# main.net
KiCad netlist of a schematic drawn in EAGLE
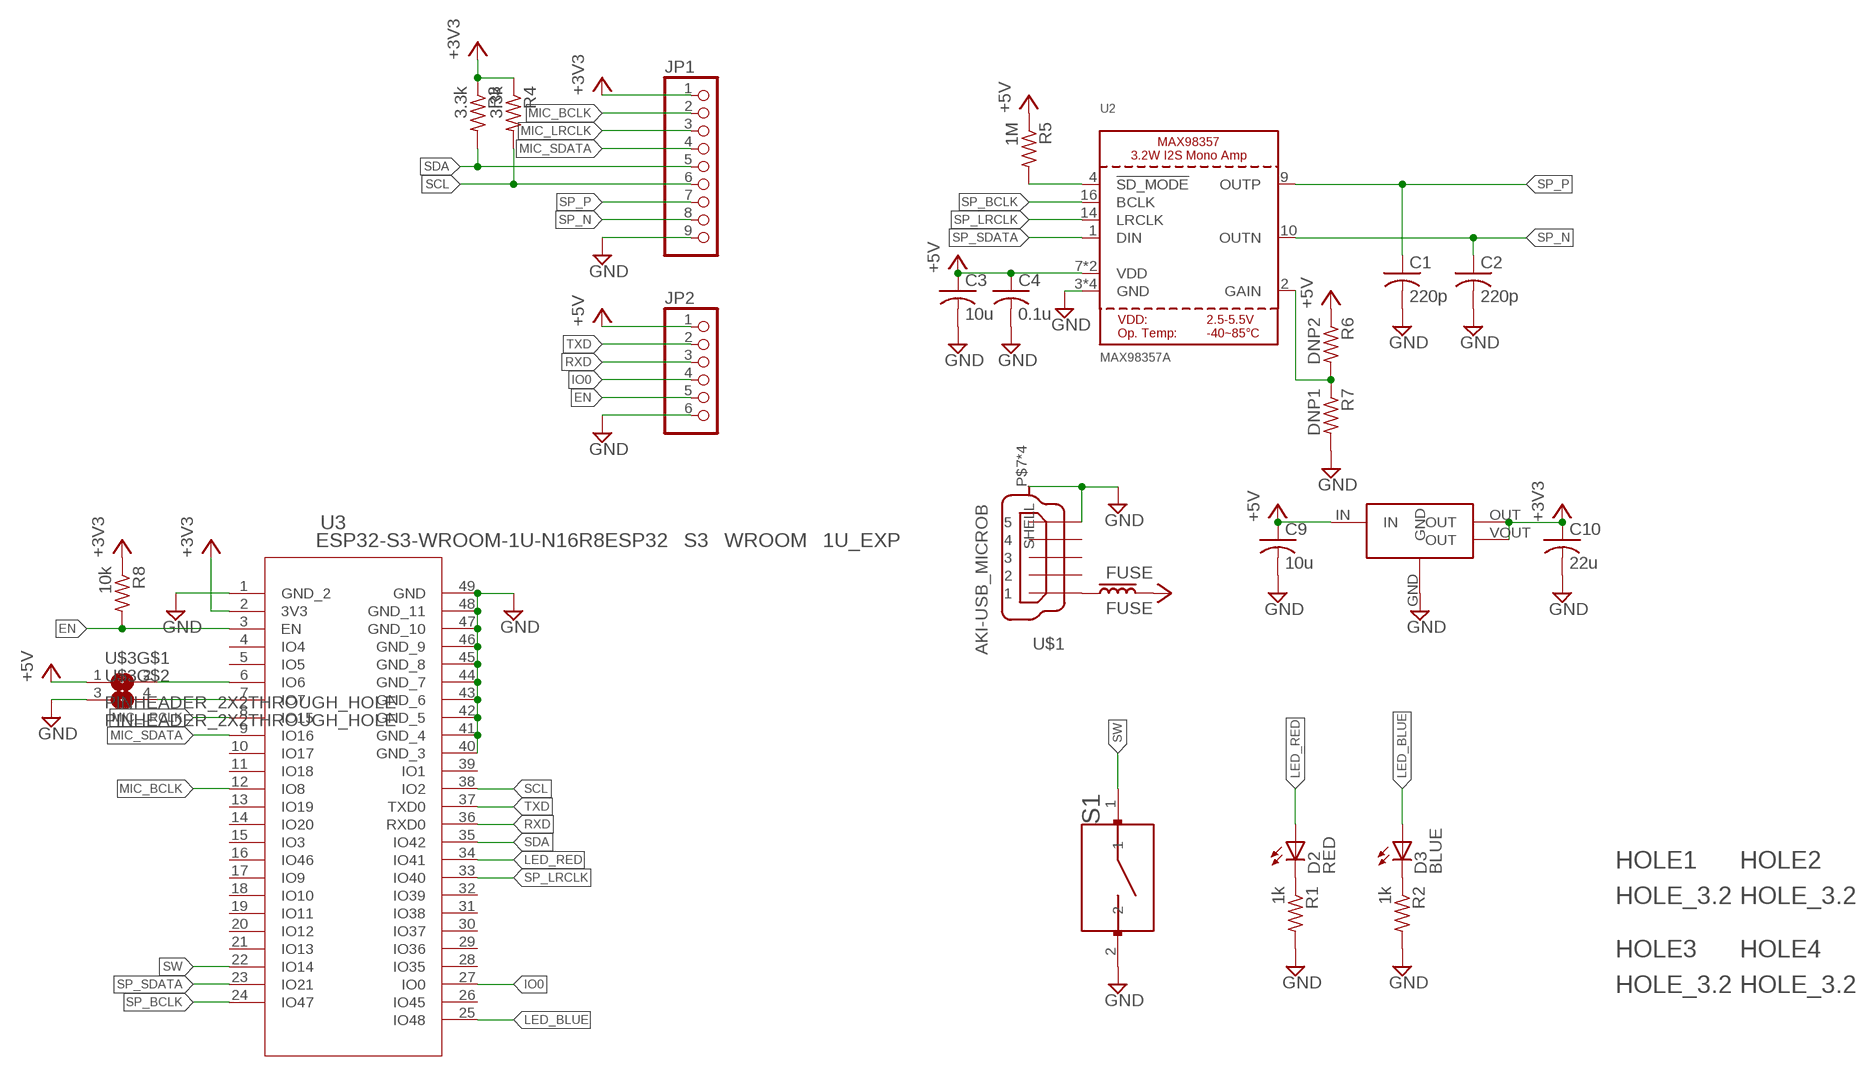
[diagram p0: schematic, sheet 1]

(export (version "E")
  (design (tool "Eeschema 10.0.6"))
  (components
    (comp (ref "C1")
      (value "220p")
      (footprint "eagle-import:2012-C")
      (libsource (lib "eagle-import") (part "C-2012"))
    )
    (comp (ref "C2")
      (value "220p")
      (footprint "eagle-import:2012-C")
      (libsource (lib "eagle-import") (part "C-2012"))
    )
    (comp (ref "C3")
      (value "10u")
      (footprint "eagle-import:2012-C")
      (libsource (lib "eagle-import") (part "C-2012"))
    )
    (comp (ref "C4")
      (value "0.1u")
      (footprint "eagle-import:2012-C")
      (libsource (lib "eagle-import") (part "C-2012"))
    )
    (comp (ref "C9")
      (value "10u")
      (footprint "eagle-import:2012-C")
      (libsource (lib "eagle-import") (part "C-2012"))
    )
    (comp (ref "C10")
      (value "22u")
      (footprint "eagle-import:2012-C")
      (libsource (lib "eagle-import") (part "C-2012"))
    )
    (comp (ref "D2")
      (value "RED")
      (footprint "eagle-import:D2012")
      (libsource (lib "eagle-import") (part "LED-SMD2012"))
    )
    (comp (ref "D3")
      (value "BLUE")
      (footprint "eagle-import:D2012")
      (libsource (lib "eagle-import") (part "LED-SMD2012"))
    )
    (comp (ref "FUSE")
      (value "FUSE")
      (footprint "eagle-import:2012-C")
      (libsource (lib "eagle-import") (part "FB-2012"))
    )
    (comp (ref "HOLE1")
      (value "HOLE_3.2")
      (footprint "eagle-import:HOLE_3.2")
      (libsource (lib "eagle-import") (part "HOLE_3.2"))
    )
    (comp (ref "HOLE2")
      (value "HOLE_3.2")
      (footprint "eagle-import:HOLE_3.2")
      (libsource (lib "eagle-import") (part "HOLE_3.2"))
    )
    (comp (ref "HOLE3")
      (value "HOLE_3.2")
      (footprint "eagle-import:HOLE_3.2")
      (libsource (lib "eagle-import") (part "HOLE_3.2"))
    )
    (comp (ref "HOLE4")
      (value "HOLE_3.2")
      (footprint "eagle-import:HOLE_3.2")
      (libsource (lib "eagle-import") (part "HOLE_3.2"))
    )
    (comp (ref "IC2")
      (value "AZ1117H-ADJ")
      (footprint "eagle-import:SOT223")
      (libsource (lib "eagle-import") (part "AZ1117H-ADJ"))
    )
    (comp (ref "JP1")
      (value "PINHD-1X9")
      (footprint "eagle-import:1X09")
      (libsource (lib "eagle-import") (part "PINHD-1X9"))
    )
    (comp (ref "JP2")
      (value "PINHD-1X6")
      (footprint "eagle-import:1X06")
      (libsource (lib "eagle-import") (part "PINHD-1X6"))
    )
    (comp (ref "R1")
      (value "1k")
      (footprint "eagle-import:2012-R")
      (libsource (lib "eagle-import") (part "R-2012"))
    )
    (comp (ref "R2")
      (value "1k")
      (footprint "eagle-import:2012-R")
      (libsource (lib "eagle-import") (part "R-2012"))
    )
    (comp (ref "R3")
      (value "3.3k")
      (footprint "eagle-import:2012-R")
      (libsource (lib "eagle-import") (part "R-2012"))
    )
    (comp (ref "R4")
      (value "3.3k")
      (footprint "eagle-import:2012-R")
      (libsource (lib "eagle-import") (part "R-2012"))
    )
    (comp (ref "R5")
      (value "1M")
      (footprint "eagle-import:2012-R")
      (libsource (lib "eagle-import") (part "R-2012"))
    )
    (comp (ref "R6")
      (value "DNP2")
      (footprint "eagle-import:2012-R")
      (libsource (lib "eagle-import") (part "R-2012"))
    )
    (comp (ref "R7")
      (value "DNP1")
      (footprint "eagle-import:2012-R")
      (libsource (lib "eagle-import") (part "R-2012"))
    )
    (comp (ref "R8")
      (value "10k")
      (footprint "eagle-import:2012-R")
      (libsource (lib "eagle-import") (part "R-2012"))
    )
    (comp (ref "S1")
      (value "TACTSW_SMD")
      (footprint "eagle-import:SW_B3U-1000P")
      (fields
        (field (name "DIGI-KEY_PART_NUMBER") "SW1021CT-ND")
        (field (name "MF") "Omron")
        (field (name "MP") "B3U-1100P")
      )
      (libsource (lib "eagle-import") (part "TACTSW_SMD"))
    )
    (comp (ref "U$1")
      (value "AKI-USB_MICROB")
      (footprint "eagle-import:ZX62R_B")
      (libsource (lib "eagle-import") (part "AKI-USB_MICROB"))
    )
    (comp (ref "U$3")
      (value "PINHEADER_2X2THROUGH_HOLE")
      (footprint "eagle-import:2X02")
      (libsource (lib "eagle-import") (part "PINHEADER_2X2THROUGH_HOLE"))
    )
    (comp (ref "U2")
      (value "MAX98357A")
      (footprint "eagle-import:QFN16_3MM")
      (libsource (lib "eagle-import") (part "AUDIOAMP_MAX98357"))
    )
    (comp (ref "U3")
      (value "ESP32-S3-WROOM-1U-N16R8ESP32�S3�WROOM�1U_EXP")
      (footprint "eagle-import:ESP32�S3�WROOM�1U_EXP")
      (fields
        (field (name "MANUFACTURER_PART_NUMBER") "ESP32-S3-WROOM-1U-N16R8")
        (field (name "COPYRIGHT") "Copyright (C) 2023 Ultra Librarian. All rights reserved.")
      )
      (libsource (lib "eagle-import") (part "ESP32-S3-WROOM-1U-N16R8ESP32�S3�WROOM�1U_EXP"))
    )
  )
  (nets
    (net (code "1") (name "+3V3") (class "Default")
      (node (ref "C10") (pin "1") (pinfunction "1_1") (pintype "passive"))
      (node (ref "IC2") (pin "OUT") (pinfunction "OUT_OUT") (pintype "power_in"))
      (node (ref "IC2") (pin "VOUT") (pinfunction "OUT_VOUT") (pintype "power_in"))
      (node (ref "JP1") (pin "1") (pinfunction "1_1") (pintype "passive"))
      (node (ref "R3") (pin "1") (pinfunction "1_1") (pintype "passive"))
      (node (ref "R4") (pin "1") (pinfunction "1_1") (pintype "passive"))
      (node (ref "R8") (pin "1") (pinfunction "1_1") (pintype "passive"))
      (node (ref "U3") (pin "2") (pinfunction "3V3_2") (pintype "power_in"))
    )
    (net (code "2") (name "+5V") (class "Default")
      (node (ref "C3") (pin "1") (pinfunction "1_1") (pintype "passive"))
      (node (ref "C4") (pin "1") (pinfunction "1_1") (pintype "passive"))
      (node (ref "C9") (pin "1") (pinfunction "1_1") (pintype "passive"))
      (node (ref "FUSE") (pin "2") (pinfunction "2_2") (pintype "passive"))
      (node (ref "IC2") (pin "IN") (pinfunction "IN_IN") (pintype "power_in"))
      (node (ref "JP2") (pin "1") (pinfunction "1_1") (pintype "passive"))
      (node (ref "R5") (pin "1") (pinfunction "1_1") (pintype "passive"))
      (node (ref "R6") (pin "1") (pinfunction "1_1") (pintype "passive"))
      (node (ref "U$3") (pin "1") (pinfunction "1_1") (pintype "passive"))
      (node (ref "U2") (pin "7") (pinfunction "VDD_7") (pintype "power_in"))
      (node (ref "U2") (pin "8") (pinfunction "VDD_8") (pintype "power_in"))
    )
    (net (code "3") (name "EN") (class "Default")
      (node (ref "JP2") (pin "5") (pinfunction "5_5") (pintype "passive"))
      (node (ref "R8") (pin "2") (pinfunction "2_2") (pintype "passive"))
      (node (ref "U3") (pin "3") (pinfunction "EN_3") (pintype "input"))
    )
    (net (code "4") (name "GND") (class "Default")
      (node (ref "C1") (pin "2") (pinfunction "2_2") (pintype "passive"))
      (node (ref "C10") (pin "2") (pinfunction "2_2") (pintype "passive"))
      (node (ref "C2") (pin "2") (pinfunction "2_2") (pintype "passive"))
      (node (ref "C3") (pin "2") (pinfunction "2_2") (pintype "passive"))
      (node (ref "C4") (pin "2") (pinfunction "2_2") (pintype "passive"))
      (node (ref "C9") (pin "2") (pinfunction "2_2") (pintype "passive"))
      (node (ref "IC2") (pin "GND") (pinfunction "GND_GND") (pintype "power_in"))
      (node (ref "JP1") (pin "9") (pinfunction "9_9") (pintype "passive"))
      (node (ref "JP2") (pin "6") (pinfunction "6_6") (pintype "passive"))
      (node (ref "R1") (pin "2") (pinfunction "2_2") (pintype "passive"))
      (node (ref "R2") (pin "2") (pinfunction "2_2") (pintype "passive"))
      (node (ref "R7") (pin "2") (pinfunction "2_2") (pintype "passive"))
      (node (ref "S1") (pin "2") (pinfunction "2_2") (pintype "passive"))
      (node (ref "U$1") (pin "5") (pinfunction "5_5") (pintype "input"))
      (node (ref "U$1") (pin "P$7") (pinfunction "SHELL_P$7") (pintype "bidirectional"))
      (node (ref "U$1") (pin "P$8") (pinfunction "SHELL_P$8") (pintype "bidirectional"))
      (node (ref "U$1") (pin "P$9") (pinfunction "SHELL_P$9") (pintype "bidirectional"))
      (node (ref "U$1") (pin "SH") (pinfunction "SHELL_SH") (pintype "bidirectional"))
      (node (ref "U$3") (pin "3") (pinfunction "1_3") (pintype "passive"))
      (node (ref "U2") (pin "11") (pinfunction "GND_11") (pintype "power_in"))
      (node (ref "U2") (pin "15") (pinfunction "GND_15") (pintype "power_in"))
      (node (ref "U2") (pin "3") (pinfunction "GND_3") (pintype "power_in"))
      (node (ref "U2") (pin "THERMAL") (pinfunction "GND_THERMAL") (pintype "power_in"))
      (node (ref "U3") (pin "1") (pinfunction "GND_2_1") (pintype "passive"))
      (node (ref "U3") (pin "40") (pinfunction "GND_3_40") (pintype "passive"))
      (node (ref "U3") (pin "41") (pinfunction "GND_4_41") (pintype "passive"))
      (node (ref "U3") (pin "42") (pinfunction "GND_5_42") (pintype "passive"))
      (node (ref "U3") (pin "43") (pinfunction "GND_6_43") (pintype "passive"))
      (node (ref "U3") (pin "44") (pinfunction "GND_7_44") (pintype "passive"))
      (node (ref "U3") (pin "45") (pinfunction "GND_8_45") (pintype "passive"))
      (node (ref "U3") (pin "46") (pinfunction "GND_9_46") (pintype "passive"))
      (node (ref "U3") (pin "47") (pinfunction "GND_10_47") (pintype "passive"))
      (node (ref "U3") (pin "48") (pinfunction "GND_11_48") (pintype "passive"))
      (node (ref "U3") (pin "49") (pinfunction "GND_49") (pintype "passive"))
    )
    (net (code "5") (name "IO0") (class "Default")
      (node (ref "JP2") (pin "4") (pinfunction "4_4") (pintype "passive"))
      (node (ref "U3") (pin "27") (pinfunction "IO0_27") (pintype "bidirectional"))
    )
    (net (code "6") (name "LED_BLUE") (class "Default")
      (node (ref "D3") (pin "A") (pinfunction "A_A") (pintype "passive"))
      (node (ref "U3") (pin "25") (pinfunction "IO48_25") (pintype "bidirectional"))
    )
    (net (code "7") (name "LED_RED") (class "Default")
      (node (ref "D2") (pin "A") (pinfunction "A_A") (pintype "passive"))
      (node (ref "U3") (pin "34") (pinfunction "IO41_34") (pintype "bidirectional"))
    )
    (net (code "8") (name "MIC_BCLK") (class "Default")
      (node (ref "JP1") (pin "2") (pinfunction "2_2") (pintype "passive"))
      (node (ref "U3") (pin "12") (pinfunction "IO8_12") (pintype "bidirectional"))
    )
    (net (code "9") (name "MIC_LRCLK") (class "Default")
      (node (ref "JP1") (pin "3") (pinfunction "3_3") (pintype "passive"))
      (node (ref "U3") (pin "8") (pinfunction "IO15_8") (pintype "bidirectional"))
    )
    (net (code "10") (name "MIC_SDATA") (class "Default")
      (node (ref "JP1") (pin "4") (pinfunction "4_4") (pintype "passive"))
      (node (ref "U3") (pin "9") (pinfunction "IO16_9") (pintype "bidirectional"))
    )
    (net (code "11") (name "Net-(D2-PadK)") (class "Default")
      (node (ref "D2") (pin "K") (pinfunction "K_K") (pintype "passive"))
      (node (ref "R1") (pin "1") (pinfunction "1_1") (pintype "passive"))
    )
    (net (code "12") (name "Net-(D3-PadK)") (class "Default")
      (node (ref "D3") (pin "K") (pinfunction "K_K") (pintype "passive"))
      (node (ref "R2") (pin "1") (pinfunction "1_1") (pintype "passive"))
    )
    (net (code "13") (name "Net-(FUSE-Pad1)") (class "Default")
      (node (ref "FUSE") (pin "1") (pinfunction "1_1") (pintype "passive"))
      (node (ref "U$1") (pin "1") (pinfunction "1_1") (pintype "input"))
    )
    (net (code "14") (name "Net-(U$3B-2)") (class "Default")
      (node (ref "U$3") (pin "4") (pinfunction "2_4") (pintype "passive"))
      (node (ref "U3") (pin "7") (pinfunction "IO7_7") (pintype "bidirectional"))
    )
    (net (code "15") (name "Net-(U2-GAIN)") (class "Default")
      (node (ref "R6") (pin "2") (pinfunction "2_2") (pintype "passive"))
      (node (ref "R7") (pin "1") (pinfunction "1_1") (pintype "passive"))
      (node (ref "U2") (pin "2") (pinfunction "GAIN_2") (pintype "bidirectional"))
    )
    (net (code "16") (name "Net-(U2-~{SD_MODE})") (class "Default")
      (node (ref "R5") (pin "2") (pinfunction "2_2") (pintype "passive"))
      (node (ref "U2") (pin "4") (pinfunction "~{SD_MODE}_4") (pintype "bidirectional"))
    )
    (net (code "17") (name "Net-(U3-IO6)") (class "Default")
      (node (ref "U$3") (pin "2") (pinfunction "2_2") (pintype "passive"))
      (node (ref "U3") (pin "6") (pinfunction "IO6_6") (pintype "bidirectional"))
    )
    (net (code "18") (name "RXD") (class "Default")
      (node (ref "JP2") (pin "3") (pinfunction "3_3") (pintype "passive"))
      (node (ref "U3") (pin "36") (pinfunction "RXD0_36") (pintype "bidirectional"))
    )
    (net (code "19") (name "SCL") (class "Default")
      (node (ref "JP1") (pin "6") (pinfunction "6_6") (pintype "passive"))
      (node (ref "R4") (pin "2") (pinfunction "2_2") (pintype "passive"))
      (node (ref "U3") (pin "38") (pinfunction "IO2_38") (pintype "bidirectional"))
    )
    (net (code "20") (name "SDA") (class "Default")
      (node (ref "JP1") (pin "5") (pinfunction "5_5") (pintype "passive"))
      (node (ref "R3") (pin "2") (pinfunction "2_2") (pintype "passive"))
      (node (ref "U3") (pin "35") (pinfunction "IO42_35") (pintype "bidirectional"))
    )
    (net (code "21") (name "SP_BCLK") (class "Default")
      (node (ref "U2") (pin "16") (pinfunction "BCLK_16") (pintype "bidirectional"))
      (node (ref "U3") (pin "24") (pinfunction "IO47_24") (pintype "bidirectional"))
    )
    (net (code "22") (name "SP_LRCLK") (class "Default")
      (node (ref "U2") (pin "14") (pinfunction "LRCLK_14") (pintype "bidirectional"))
      (node (ref "U3") (pin "33") (pinfunction "IO40_33") (pintype "bidirectional"))
    )
    (net (code "23") (name "SP_N") (class "Default")
      (node (ref "C2") (pin "1") (pinfunction "1_1") (pintype "passive"))
      (node (ref "JP1") (pin "8") (pinfunction "8_8") (pintype "passive"))
      (node (ref "U2") (pin "10") (pinfunction "OUTN_10") (pintype "output"))
    )
    (net (code "24") (name "SP_P") (class "Default")
      (node (ref "C1") (pin "1") (pinfunction "1_1") (pintype "passive"))
      (node (ref "JP1") (pin "7") (pinfunction "7_7") (pintype "passive"))
      (node (ref "U2") (pin "9") (pinfunction "OUTP_9") (pintype "output"))
    )
    (net (code "25") (name "SP_SDATA") (class "Default")
      (node (ref "U2") (pin "1") (pinfunction "DIN_1") (pintype "bidirectional"))
      (node (ref "U3") (pin "23") (pinfunction "IO21_23") (pintype "bidirectional"))
    )
    (net (code "26") (name "SW") (class "Default")
      (node (ref "S1") (pin "1") (pinfunction "1_1") (pintype "passive"))
      (node (ref "U3") (pin "22") (pinfunction "IO14_22") (pintype "bidirectional"))
    )
    (net (code "27") (name "TXD") (class "Default")
      (node (ref "JP2") (pin "2") (pinfunction "2_2") (pintype "passive"))
      (node (ref "U3") (pin "37") (pinfunction "TXD0_37") (pintype "bidirectional"))
    )
    (net (code "28") (name "unconnected-(U$1-Pad2)") (class "Default")
      (node (ref "U$1") (pin "2") (pinfunction "2_2") (pintype "input"))
    )
    (net (code "29") (name "unconnected-(U$1-Pad3)") (class "Default")
      (node (ref "U$1") (pin "3") (pinfunction "3_3") (pintype "input"))
    )
    (net (code "30") (name "unconnected-(U$1-Pad4)") (class "Default")
      (node (ref "U$1") (pin "4") (pinfunction "4_4") (pintype "input"))
    )
    (net (code "31") (name "unconnected-(U3-IO1-Pad39)") (class "Default")
      (node (ref "U3") (pin "39") (pinfunction "IO1_39") (pintype "bidirectional"))
    )
    (net (code "32") (name "unconnected-(U3-IO3-Pad15)") (class "Default")
      (node (ref "U3") (pin "15") (pinfunction "IO3_15") (pintype "bidirectional"))
    )
    (net (code "33") (name "unconnected-(U3-IO4-Pad4)") (class "Default")
      (node (ref "U3") (pin "4") (pinfunction "IO4_4") (pintype "bidirectional"))
    )
    (net (code "34") (name "unconnected-(U3-IO5-Pad5)") (class "Default")
      (node (ref "U3") (pin "5") (pinfunction "IO5_5") (pintype "bidirectional"))
    )
    (net (code "35") (name "unconnected-(U3-IO9-Pad17)") (class "Default")
      (node (ref "U3") (pin "17") (pinfunction "IO9_17") (pintype "bidirectional"))
    )
    (net (code "36") (name "unconnected-(U3-IO10-Pad18)") (class "Default")
      (node (ref "U3") (pin "18") (pinfunction "IO10_18") (pintype "bidirectional"))
    )
    (net (code "37") (name "unconnected-(U3-IO11-Pad19)") (class "Default")
      (node (ref "U3") (pin "19") (pinfunction "IO11_19") (pintype "bidirectional"))
    )
    (net (code "38") (name "unconnected-(U3-IO12-Pad20)") (class "Default")
      (node (ref "U3") (pin "20") (pinfunction "IO12_20") (pintype "bidirectional"))
    )
    (net (code "39") (name "unconnected-(U3-IO13-Pad21)") (class "Default")
      (node (ref "U3") (pin "21") (pinfunction "IO13_21") (pintype "bidirectional"))
    )
    (net (code "40") (name "unconnected-(U3-IO17-Pad10)") (class "Default")
      (node (ref "U3") (pin "10") (pinfunction "IO17_10") (pintype "bidirectional"))
    )
    (net (code "41") (name "unconnected-(U3-IO18-Pad11)") (class "Default")
      (node (ref "U3") (pin "11") (pinfunction "IO18_11") (pintype "bidirectional"))
    )
    (net (code "42") (name "unconnected-(U3-IO19-Pad13)") (class "Default")
      (node (ref "U3") (pin "13") (pinfunction "IO19_13") (pintype "bidirectional"))
    )
    (net (code "43") (name "unconnected-(U3-IO20-Pad14)") (class "Default")
      (node (ref "U3") (pin "14") (pinfunction "IO20_14") (pintype "bidirectional"))
    )
    (net (code "44") (name "unconnected-(U3-IO35-Pad28)") (class "Default")
      (node (ref "U3") (pin "28") (pinfunction "IO35_28") (pintype "bidirectional"))
    )
    (net (code "45") (name "unconnected-(U3-IO36-Pad29)") (class "Default")
      (node (ref "U3") (pin "29") (pinfunction "IO36_29") (pintype "bidirectional"))
    )
    (net (code "46") (name "unconnected-(U3-IO37-Pad30)") (class "Default")
      (node (ref "U3") (pin "30") (pinfunction "IO37_30") (pintype "bidirectional"))
    )
    (net (code "47") (name "unconnected-(U3-IO38-Pad31)") (class "Default")
      (node (ref "U3") (pin "31") (pinfunction "IO38_31") (pintype "bidirectional"))
    )
    (net (code "48") (name "unconnected-(U3-IO39-Pad32)") (class "Default")
      (node (ref "U3") (pin "32") (pinfunction "IO39_32") (pintype "bidirectional"))
    )
    (net (code "49") (name "unconnected-(U3-IO45-Pad26)") (class "Default")
      (node (ref "U3") (pin "26") (pinfunction "IO45_26") (pintype "bidirectional"))
    )
    (net (code "50") (name "unconnected-(U3-IO46-Pad16)") (class "Default")
      (node (ref "U3") (pin "16") (pinfunction "IO46_16") (pintype "bidirectional"))
    )
  )
)
